# 3_BLE-T1-mcu.net
KiCad netlist of a schematic drawn in Altium Designer
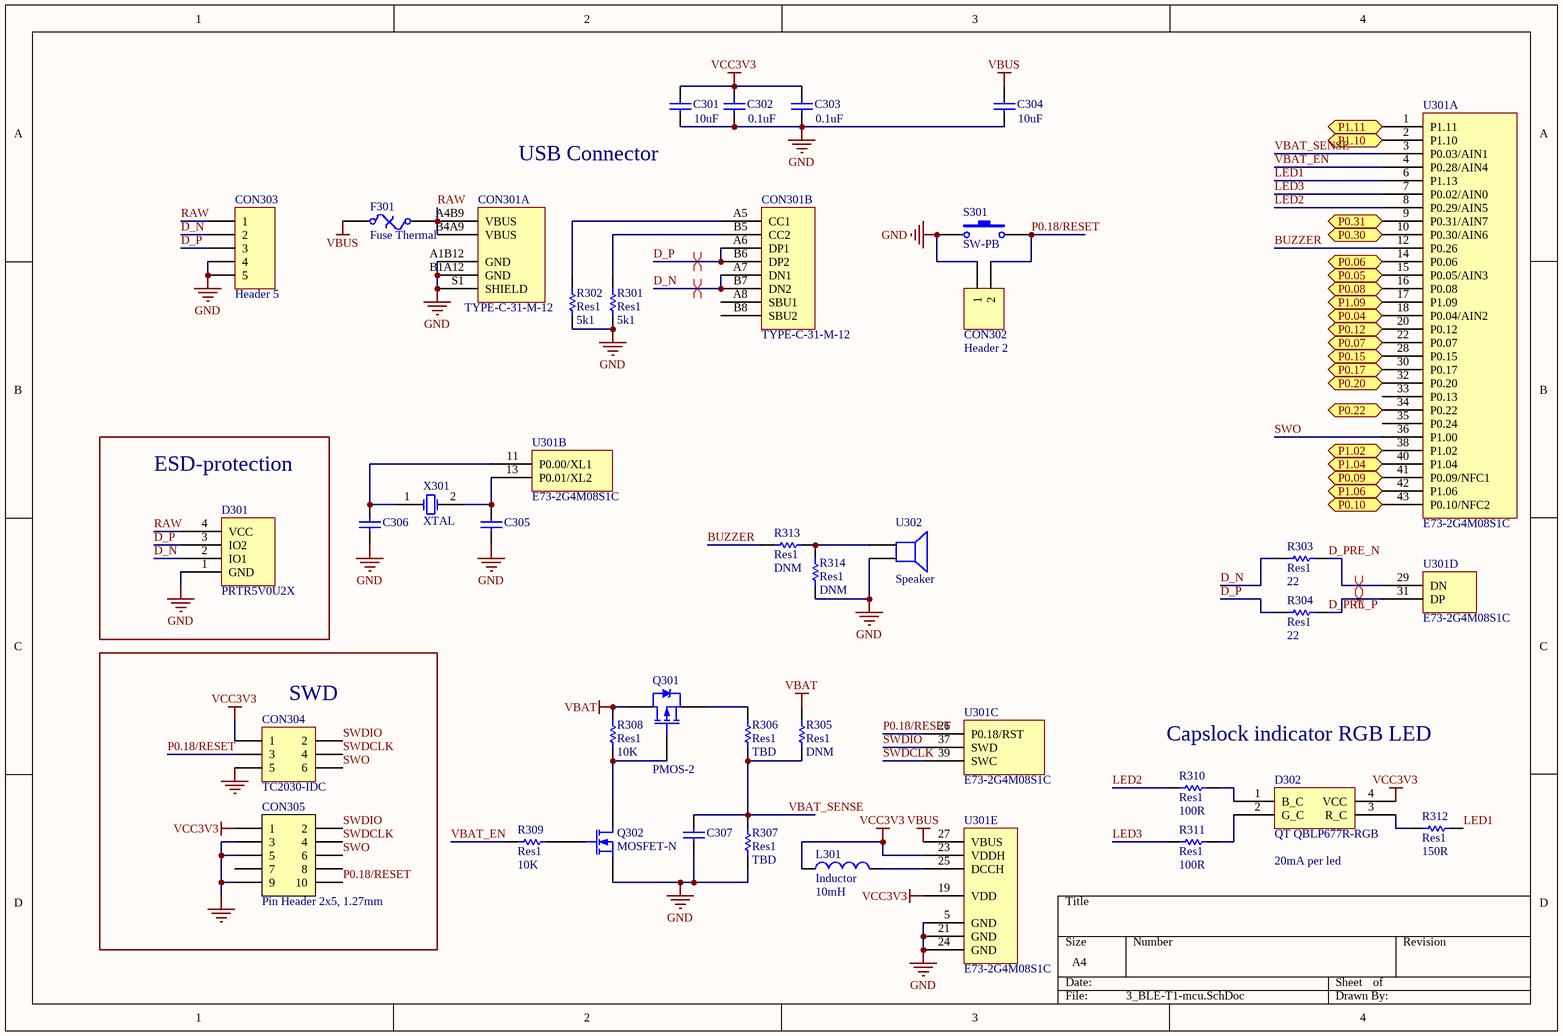
[diagram p0: 3_BLE-T1-mcu.SchDoc]

(export (version "E")
  (design (tool "Eeschema 10.0.6"))
  (components
    (comp (ref "C301")
      (value "10uF")
      (footprint "C1206[3216]")
      (description "Capacitor")
      (fields (field (name "MFG") "KEMET") (field (name "MRF.PART") "C3216X7R1C106KT000N"))
      (libsource (lib "Miscellaneous Devices") (part "Cap"))
    )
    (comp (ref "C302")
      (value "0.1uF")
      (footprint "C0603[1608]")
      (description "Capacitor")
      (fields (field (name "MFG") "KEMET") (field (name "MRF.PART") "CC0603KRX7R9BB104"))
      (libsource (lib "Miscellaneous Devices") (part "Cap"))
    )
    (comp (ref "C303")
      (value "0.1uF")
      (footprint "C0603[1608]")
      (description "Capacitor")
      (fields (field (name "MFG") "KEMET") (field (name "MRF.PART") "CC0603KRX7R9BB104"))
      (libsource (lib "Miscellaneous Devices") (part "Cap"))
    )
    (comp (ref "C304")
      (value "10uF")
      (footprint "C1206[3216]")
      (description "Capacitor")
      (fields (field (name "MFG") "KEMET") (field (name "MRF.PART") "C3216X7R1C106KT000N"))
      (libsource (lib "Miscellaneous Devices") (part "Cap"))
    )
    (comp (ref "C305")
      (value "~")
      (footprint "C0603[1608]")
      (description "Capacitor")
      (libsource (lib "Miscellaneous Devices") (part "Cap"))
    )
    (comp (ref "C306")
      (value "~")
      (footprint "C0603[1608]")
      (description "Capacitor")
      (libsource (lib "Miscellaneous Devices") (part "Cap"))
    )
    (comp (ref "C307")
      (value "~")
      (footprint "C0603[1608]")
      (description "Capacitor")
      (libsource (lib "Miscellaneous Devices") (part "Cap"))
    )
    (comp (ref "CON301")
      (value "TYPE-C-31-M-12")
      (footprint "TYPE-C-31-M-12")
      (fields (field (name "MFG") "Korean Hroparts Elec") (field (name "LCSC PART #") "C165948"))
      (libsource (lib "Schlib1") (part "TYPE-C-31-M-12"))
    )
    (comp (ref "CON302")
      (value "Header 2")
      (footprint "HDR1X2")
      (description "Header, 2-Pin")
      (fields (field (name "PUBLISHER") "Altium Limited"))
      (libsource (lib "Miscellaneous Connectors") (part "Header 2"))
    )
    (comp (ref "CON303")
      (value "Header 5")
      (footprint "JST SM04B-SRSS-TB")
      (description "JST for USB daughter board")
      (fields (field (name "MFG") "JST Sales America Inc.") (field (name "LCSC PART #") "C160404"))
      (libsource (lib "Miscellaneous Connectors") (part "Header 5"))
    )
    (comp (ref "CON304")
      (value "TC2030-IDC")
      (footprint "TC2030-IDC-NL")
      (description "Header, 3-Pin, Dual row")
      (libsource (lib "Miscellaneous Connectors") (part "Header 3X2"))
    )
    (comp (ref "CON305")
      (value "Pin Header 2x5, 1.27mm")
      (footprint "HDR_2x5-SMD-1.27mm-K")
      (description "Pin Header 2x5, 1.27mm (50mil), SMD, Keying Shroud")
      (fields (field (name "MFG") "Samtec Inc."))
      (libsource (lib "Nordic Passive DB") (part "CONN-2x5"))
    )
    (comp (ref "D301")
      (value "PRTR5V0U2X")
      (footprint "SOT190P237X120-4N")
      (fields
        (field (name "MFG") "Nexperia USA Inc.")
        (field (name "LCSC PART #") "C78442")
        (field (name "MRF.PART") "UET14A05L03")
      )
      (libsource (lib "Schlib1") (part "PRTR5V0U2X"))
    )
    (comp (ref "D302")
      (value "QT QBLP677R-RGB")
      (footprint "QT QBLP677R-RGB")
      (description "RGB LED")
      (fields (field (name "MFG") "QT Brightek (QTB)"))
      (libsource (lib "Keebs") (part "QT QBLP677R-RGB"))
    )
    (comp (ref "F301")
      (value "Fuse Thermal")
      (footprint "C1206[3216]")
      (description "Thermal Fuse")
      (fields (field (name "MFG") "Bel Fuse Inc.") (field (name "LCSC PART #") "C135338"))
      (libsource (lib "Miscellaneous Devices") (part "Fuse Thermal"))
    )
    (comp (ref "L301")
      (value "Inductor")
      (footprint "C0603[1608]")
      (fields (field (name "ALTIUM_VALUE") "10mH") (field (name "PUBLISHER") "Altium Limited"))
      (libsource (lib "Miscellaneous Devices") (part "Inductor"))
    )
    (comp (ref "Q301")
      (value "PMOS-2")
      (footprint "SOT-23-3")
      (description "P-Channel Power MOSFET")
      (fields (field (name "PUBLISHER") "Altium Limited"))
      (libsource (lib "Miscellaneous Devices") (part "PMOS-2"))
    )
    (comp (ref "Q302")
      (value "MOSFET-N")
      (footprint "SOT-23-3")
      (description "N-Channel MOSFET")
      (fields (field (name "PUBLISHER") "Altium Limited"))
      (libsource (lib "Miscellaneous Devices") (part "MOSFET-N"))
    )
    (comp (ref "R301")
      (value "Res1")
      (footprint "R0603[1608]")
      (description "Resistor")
      (fields
        (field (name "ALTIUM_VALUE") "5k1")
        (field (name "MFG") "Panasonic Electronic Components")
        (field (name "LCSC PART #") "C23186")
      )
      (libsource (lib "Miscellaneous Devices") (part "Res1"))
    )
    (comp (ref "R302")
      (value "Res1")
      (footprint "R0603[1608]")
      (description "Resistor")
      (fields
        (field (name "ALTIUM_VALUE") "5k1")
        (field (name "MFG") "Panasonic Electronic Components")
        (field (name "LCSC PART #") "C23186")
      )
      (libsource (lib "Miscellaneous Devices") (part "Res1"))
    )
    (comp (ref "R303")
      (value "Res1")
      (footprint "R0603[1608]")
      (description "Resistor")
      (fields
        (field (name "ALTIUM_VALUE") "22")
        (field (name "MFG") "Panasonic Electronic Components")
        (field (name "LCSC PART #") "C23345")
      )
      (libsource (lib "Miscellaneous Devices") (part "Res1"))
    )
    (comp (ref "R304")
      (value "Res1")
      (footprint "R0603[1608]")
      (description "Resistor")
      (fields
        (field (name "ALTIUM_VALUE") "22")
        (field (name "MFG") "Panasonic Electronic Components")
        (field (name "LCSC PART #") "C23345")
      )
      (libsource (lib "Miscellaneous Devices") (part "Res1"))
    )
    (comp (ref "R305")
      (value "Res1")
      (footprint "R0603[1608]")
      (description "Resistor")
      (fields (field (name "ALTIUM_VALUE") "DNM") (field (name "MFG") "TE Connectivity Passive Product"))
      (libsource (lib "Miscellaneous Devices") (part "Res1"))
    )
    (comp (ref "R306")
      (value "Res1")
      (footprint "R0603[1608]")
      (description "Resistor")
      (fields (field (name "ALTIUM_VALUE") "TBD") (field (name "MFG") "TE Connectivity Passive Product"))
      (libsource (lib "Miscellaneous Devices") (part "Res1"))
    )
    (comp (ref "R307")
      (value "Res1")
      (footprint "R0603[1608]")
      (description "Resistor")
      (fields (field (name "ALTIUM_VALUE") "TBD") (field (name "MFG") "TE Connectivity Passive Product"))
      (libsource (lib "Miscellaneous Devices") (part "Res1"))
    )
    (comp (ref "R308")
      (value "Res1")
      (footprint "R0603[1608]")
      (description "Resistor")
      (fields (field (name "ALTIUM_VALUE") "10K") (field (name "MFG") "TE Connectivity Passive Product"))
      (libsource (lib "Miscellaneous Devices") (part "Res1"))
    )
    (comp (ref "R309")
      (value "Res1")
      (footprint "R0603[1608]")
      (description "Resistor")
      (fields (field (name "ALTIUM_VALUE") "10K") (field (name "MFG") "TE Connectivity Passive Product"))
      (libsource (lib "Miscellaneous Devices") (part "Res1"))
    )
    (comp (ref "R310")
      (value "Res1")
      (footprint "R0603[1608]")
      (description "Resistor")
      (fields (field (name "ALTIUM_VALUE") "100R") (field (name "MFG") "TE Connectivity Passive Product"))
      (libsource (lib "Miscellaneous Devices") (part "Res1"))
    )
    (comp (ref "R311")
      (value "Res1")
      (footprint "R0603[1608]")
      (description "Resistor")
      (fields (field (name "ALTIUM_VALUE") "100R") (field (name "MFG") "TE Connectivity Passive Product"))
      (libsource (lib "Miscellaneous Devices") (part "Res1"))
    )
    (comp (ref "R312")
      (value "Res1")
      (footprint "R0603[1608]")
      (description "Resistor")
      (fields (field (name "ALTIUM_VALUE") "150R") (field (name "MFG") "TE Connectivity Passive Product"))
      (libsource (lib "Miscellaneous Devices") (part "Res1"))
    )
    (comp (ref "R313")
      (value "Res1")
      (footprint "R0603[1608]")
      (description "Resistor")
      (fields
        (field (name "ALTIUM_VALUE") "DNM")
        (field (name "MFG") "Panasonic Electronic Components")
        (field (name "LCSC PART #") "C23345")
      )
      (libsource (lib "Miscellaneous Devices") (part "Res1"))
    )
    (comp (ref "R314")
      (value "Res1")
      (footprint "R0603[1608]")
      (description "Resistor")
      (fields
        (field (name "ALTIUM_VALUE") "DNM")
        (field (name "MFG") "Panasonic Electronic Components")
        (field (name "LCSC PART #") "C23345")
      )
      (libsource (lib "Miscellaneous Devices") (part "Res1"))
    )
    (comp (ref "S301")
      (value "SW-PB")
      (footprint "Combo switch")
      (description "Switch")
      (fields (field (name "MFG") "C&K") (field (name "MRF.PART") "TS-1187A-C-D-B"))
      (libsource (lib "Miscellaneous Devices") (part "SW-PB"))
    )
    (comp (ref "U301")
      (value "E73-2G4M08S1C")
      (footprint "E73-2G4M08S1C BLE-T1")
      (libsource (lib "Keebs") (part "E73-2G4M08S1C"))
    )
    (comp (ref "U302")
      (value "Speaker")
      (footprint "buzzer 12x12")
      (description "Loudspeaker")
      (fields (field (name "PUBLISHER") "Altium Limited"))
      (libsource (lib "Miscellaneous Devices") (part "Speaker"))
    )
    (comp (ref "X301")
      (value "XTAL")
      (footprint "Seiko Epson Q13FC1350000400")
      (description "Crystal Oscillator")
      (fields (field (name "LCSC PART #") "C32346") (field (name "MRF.PART") "Q13FC1350000400"))
      (libsource (lib "Miscellaneous Devices") (part "XTAL"))
    )
  )
  (nets
    (net (code "1") (name "/BUZZER") (class "Default")
      (node (ref "R313") (pin "1") (pinfunction "1_1") (pintype "passive"))
      (node (ref "U301") (pin "12") (pinfunction "P0.26_12") (pintype "passive"))
    )
    (net (code "2") (name "/D_N") (class "Default")
      (node (ref "CON301") (pin "A7") (pinfunction "DN1_A7") (pintype "passive"))
      (node (ref "CON301") (pin "B7") (pinfunction "DN2_B7") (pintype "passive"))
      (node (ref "CON303") (pin "2") (pinfunction "2_2") (pintype "passive"))
      (node (ref "D301") (pin "2") (pinfunction "IO1_2") (pintype "passive"))
      (node (ref "R303") (pin "2") (pinfunction "2_2") (pintype "passive"))
    )
    (net (code "3") (name "/D_P") (class "Default")
      (node (ref "CON301") (pin "A6") (pinfunction "DP1_A6") (pintype "passive"))
      (node (ref "CON301") (pin "B6") (pinfunction "DP2_B6") (pintype "passive"))
      (node (ref "CON303") (pin "3") (pinfunction "3_3") (pintype "passive"))
      (node (ref "D301") (pin "3") (pinfunction "IO2_3") (pintype "passive"))
      (node (ref "R304") (pin "2") (pinfunction "2_2") (pintype "passive"))
    )
    (net (code "4") (name "/D_PRE_N") (class "Default")
      (node (ref "R303") (pin "1") (pinfunction "1_1") (pintype "passive"))
      (node (ref "U301") (pin "29") (pinfunction "DN_29") (pintype "passive"))
    )
    (net (code "5") (name "/D_PRE_P") (class "Default")
      (node (ref "R304") (pin "1") (pinfunction "1_1") (pintype "passive"))
      (node (ref "U301") (pin "31") (pinfunction "DP_31") (pintype "passive"))
    )
    (net (code "6") (name "/LED1") (class "Default")
      (node (ref "R312") (pin "1") (pinfunction "1_1") (pintype "passive"))
      (node (ref "U301") (pin "6") (pinfunction "P1.13_6") (pintype "passive"))
    )
    (net (code "7") (name "/LED2") (class "Default")
      (node (ref "R310") (pin "2") (pinfunction "2_2") (pintype "passive"))
      (node (ref "U301") (pin "8") (pinfunction "P0.29/AIN5_8") (pintype "passive"))
    )
    (net (code "8") (name "/LED3") (class "Default")
      (node (ref "R311") (pin "2") (pinfunction "2_2") (pintype "passive"))
      (node (ref "U301") (pin "7") (pinfunction "P0.02/AIN0_7") (pintype "passive"))
    )
    (net (code "9") (name "/P0.04") (class "Default")
      (node (ref "U301") (pin "18") (pinfunction "P0.04/AIN2_18") (pintype "passive"))
    )
    (net (code "10") (name "/P0.05") (class "Default")
      (node (ref "U301") (pin "15") (pinfunction "P0.05/AIN3_15") (pintype "passive"))
    )
    (net (code "11") (name "/P0.06") (class "Default")
      (node (ref "U301") (pin "14") (pinfunction "P0.06_14") (pintype "passive"))
    )
    (net (code "12") (name "/P0.07") (class "Default")
      (node (ref "U301") (pin "22") (pinfunction "P0.07_22") (pintype "passive"))
    )
    (net (code "13") (name "/P0.08") (class "Default")
      (node (ref "U301") (pin "16") (pinfunction "P0.08_16") (pintype "passive"))
    )
    (net (code "14") (name "/P0.09") (class "Default")
      (node (ref "U301") (pin "41") (pinfunction "P0.09/NFC1_41") (pintype "passive"))
    )
    (net (code "15") (name "/P0.10") (class "Default")
      (node (ref "U301") (pin "43") (pinfunction "P0.10/NFC2_43") (pintype "passive"))
    )
    (net (code "16") (name "/P0.12") (class "Default")
      (node (ref "U301") (pin "20") (pinfunction "P0.12_20") (pintype "passive"))
    )
    (net (code "17") (name "/P0.15") (class "Default")
      (node (ref "U301") (pin "28") (pinfunction "P0.15_28") (pintype "passive"))
    )
    (net (code "18") (name "/P0.17") (class "Default")
      (node (ref "U301") (pin "30") (pinfunction "P0.17_30") (pintype "passive"))
    )
    (net (code "19") (name "/P0.18{slash}RESET") (class "Default")
      (node (ref "CON302") (pin "2") (pinfunction "2_2") (pintype "passive"))
      (node (ref "CON304") (pin "3") (pinfunction "3_3") (pintype "passive"))
      (node (ref "CON305") (pin "10") (pinfunction "10_10") (pintype "passive"))
      (node (ref "S301") (pin "2") (pinfunction "2_2") (pintype "passive"))
      (node (ref "U301") (pin "26") (pinfunction "P0.18/RST_26") (pintype "passive"))
    )
    (net (code "20") (name "/P0.20") (class "Default")
      (node (ref "U301") (pin "32") (pinfunction "P0.20_32") (pintype "passive"))
    )
    (net (code "21") (name "/P0.22") (class "Default")
      (node (ref "U301") (pin "34") (pinfunction "P0.22_34") (pintype "passive"))
    )
    (net (code "22") (name "/P0.30") (class "Default")
      (node (ref "U301") (pin "10") (pinfunction "P0.30/AIN6_10") (pintype "passive"))
    )
    (net (code "23") (name "/P0.31") (class "Default")
      (node (ref "U301") (pin "9") (pinfunction "P0.31/AIN7_9") (pintype "passive"))
    )
    (net (code "24") (name "/P1.02") (class "Default")
      (node (ref "U301") (pin "38") (pinfunction "P1.02_38") (pintype "passive"))
    )
    (net (code "25") (name "/P1.04") (class "Default")
      (node (ref "U301") (pin "40") (pinfunction "P1.04_40") (pintype "passive"))
    )
    (net (code "26") (name "/P1.06") (class "Default")
      (node (ref "U301") (pin "42") (pinfunction "P1.06_42") (pintype "passive"))
    )
    (net (code "27") (name "/P1.09") (class "Default")
      (node (ref "U301") (pin "17") (pinfunction "P1.09_17") (pintype "passive"))
    )
    (net (code "28") (name "/P1.10") (class "Default")
      (node (ref "U301") (pin "2") (pinfunction "P1.10_2") (pintype "passive"))
    )
    (net (code "29") (name "/P1.11") (class "Default")
      (node (ref "U301") (pin "1") (pinfunction "P1.11_1") (pintype "passive"))
    )
    (net (code "30") (name "/RAW") (class "Default")
      (node (ref "CON301") (pin "A4B9") (pinfunction "VBUS_A4B9") (pintype "passive"))
      (node (ref "CON301") (pin "B4A9") (pinfunction "VBUS_B4A9") (pintype "passive"))
      (node (ref "CON303") (pin "1") (pinfunction "1_1") (pintype "passive"))
      (node (ref "D301") (pin "4") (pinfunction "VCC_4") (pintype "passive"))
      (node (ref "F301") (pin "2") (pinfunction "2_2") (pintype "passive"))
    )
    (net (code "31") (name "/SWDCLK") (class "Default")
      (node (ref "CON304") (pin "4") (pinfunction "4_4") (pintype "passive"))
      (node (ref "CON305") (pin "4") (pinfunction "4_4") (pintype "passive"))
      (node (ref "U301") (pin "39") (pinfunction "SWC_39") (pintype "passive"))
    )
    (net (code "32") (name "/SWDIO") (class "Default")
      (node (ref "CON304") (pin "2") (pinfunction "2_2") (pintype "passive"))
      (node (ref "CON305") (pin "2") (pinfunction "2_2") (pintype "passive"))
      (node (ref "U301") (pin "37") (pinfunction "SWD_37") (pintype "passive"))
    )
    (net (code "33") (name "/SWO") (class "Default")
      (node (ref "CON304") (pin "6") (pinfunction "6_6") (pintype "passive"))
      (node (ref "CON305") (pin "6") (pinfunction "6_6") (pintype "passive"))
      (node (ref "U301") (pin "36") (pinfunction "P1.00_36") (pintype "passive"))
    )
    (net (code "34") (name "/VBAT_EN") (class "Default")
      (node (ref "R309") (pin "2") (pinfunction "2_2") (pintype "passive"))
      (node (ref "U301") (pin "4") (pinfunction "P0.28/AIN4_4") (pintype "passive"))
    )
    (net (code "35") (name "/VBAT_SENSE") (class "Default")
      (node (ref "C307") (pin "2") (pinfunction "2_2") (pintype "passive"))
      (node (ref "R305") (pin "1") (pinfunction "1_1") (pintype "passive"))
      (node (ref "R306") (pin "1") (pinfunction "1_1") (pintype "passive"))
      (node (ref "R307") (pin "2") (pinfunction "2_2") (pintype "passive"))
      (node (ref "U301") (pin "3") (pinfunction "P0.03/AIN1_3") (pintype "passive"))
    )
    (net (code "36") (name "GND") (class "Default")
      (node (ref "C301") (pin "1") (pinfunction "1_1") (pintype "passive"))
      (node (ref "C302") (pin "1") (pinfunction "1_1") (pintype "passive"))
      (node (ref "C303") (pin "1") (pinfunction "1_1") (pintype "passive"))
      (node (ref "C304") (pin "1") (pinfunction "1_1") (pintype "passive"))
      (node (ref "C305") (pin "1") (pinfunction "1_1") (pintype "passive"))
      (node (ref "C306") (pin "1") (pinfunction "1_1") (pintype "passive"))
      (node (ref "C307") (pin "1") (pinfunction "1_1") (pintype "passive"))
      (node (ref "CON301") (pin "A1B12") (pinfunction "GND_A1B12") (pintype "passive"))
      (node (ref "CON301") (pin "B1A12") (pinfunction "GND_B1A12") (pintype "passive"))
      (node (ref "CON301") (pin "S1") (pinfunction "SHIELD_S1") (pintype "passive"))
      (node (ref "CON302") (pin "1") (pinfunction "1_1") (pintype "passive"))
      (node (ref "CON303") (pin "4") (pinfunction "4_4") (pintype "passive"))
      (node (ref "CON303") (pin "5") (pinfunction "5_5") (pintype "passive"))
      (node (ref "CON304") (pin "5") (pinfunction "5_5") (pintype "passive"))
      (node (ref "CON305") (pin "3") (pinfunction "3_3") (pintype "passive"))
      (node (ref "CON305") (pin "5") (pinfunction "5_5") (pintype "passive"))
      (node (ref "CON305") (pin "9") (pinfunction "9_9") (pintype "passive"))
      (node (ref "D301") (pin "1") (pinfunction "GND_1") (pintype "passive"))
      (node (ref "Q302") (pin "2") (pinfunction "S_2") (pintype "passive"))
      (node (ref "R301") (pin "2") (pinfunction "2_2") (pintype "passive"))
      (node (ref "R302") (pin "2") (pinfunction "2_2") (pintype "passive"))
      (node (ref "R307") (pin "1") (pinfunction "1_1") (pintype "passive"))
      (node (ref "R314") (pin "1") (pinfunction "1_1") (pintype "passive"))
      (node (ref "S301") (pin "1") (pinfunction "1_1") (pintype "passive"))
      (node (ref "U301") (pin "21") (pinfunction "GND_21") (pintype "passive"))
      (node (ref "U301") (pin "24") (pinfunction "GND_24") (pintype "passive"))
      (node (ref "U301") (pin "5") (pinfunction "GND_5") (pintype "passive"))
      (node (ref "U302") (pin "2") (pinfunction "2_2") (pintype "passive"))
    )
    (net (code "37") (name "Net-(CON301B-CC1)") (class "Default")
      (node (ref "CON301") (pin "A5") (pinfunction "CC1_A5") (pintype "passive"))
      (node (ref "R302") (pin "1") (pinfunction "1_1") (pintype "passive"))
    )
    (net (code "38") (name "Net-(CON301B-CC2)") (class "Default")
      (node (ref "CON301") (pin "B5") (pinfunction "CC2_B5") (pintype "passive"))
      (node (ref "R301") (pin "1") (pinfunction "1_1") (pintype "passive"))
    )
    (net (code "39") (name "Net-(D302-B_C)") (class "Default")
      (node (ref "D302") (pin "1") (pinfunction "B_C_1") (pintype "passive"))
      (node (ref "R310") (pin "1") (pinfunction "1_1") (pintype "passive"))
    )
    (net (code "40") (name "Net-(D302-G_C)") (class "Default")
      (node (ref "D302") (pin "2") (pinfunction "G_C_2") (pintype "passive"))
      (node (ref "R311") (pin "1") (pinfunction "1_1") (pintype "passive"))
    )
    (net (code "41") (name "Net-(D302-R_C)") (class "Default")
      (node (ref "D302") (pin "3") (pinfunction "R_C_3") (pintype "passive"))
      (node (ref "R312") (pin "2") (pinfunction "2_2") (pintype "passive"))
    )
    (net (code "42") (name "Net-(Q301-G)") (class "Default")
      (node (ref "Q301") (pin "1") (pinfunction "G_1") (pintype "passive"))
      (node (ref "Q302") (pin "3") (pinfunction "D_3") (pintype "passive"))
      (node (ref "R308") (pin "1") (pinfunction "1_1") (pintype "passive"))
    )
    (net (code "43") (name "Net-(Q301-S)") (class "Default")
      (node (ref "Q301") (pin "2") (pinfunction "S_2") (pintype "passive"))
      (node (ref "R306") (pin "2") (pinfunction "2_2") (pintype "passive"))
    )
    (net (code "44") (name "Net-(Q302-G)") (class "Default")
      (node (ref "Q302") (pin "1") (pinfunction "G_1") (pintype "passive"))
      (node (ref "R309") (pin "1") (pinfunction "1_1") (pintype "passive"))
    )
    (net (code "45") (name "Net-(R313-Pad2)") (class "Default")
      (node (ref "R313") (pin "2") (pinfunction "2_2") (pintype "passive"))
      (node (ref "R314") (pin "2") (pinfunction "2_2") (pintype "passive"))
      (node (ref "U302") (pin "1") (pinfunction "1_1") (pintype "passive"))
    )
    (net (code "46") (name "Net-(U301B-P0.00{slash}XL1)") (class "Default")
      (node (ref "C306") (pin "2") (pinfunction "2_2") (pintype "passive"))
      (node (ref "U301") (pin "11") (pinfunction "P0.00/XL1_11") (pintype "passive"))
      (node (ref "X301") (pin "1") (pinfunction "OSC1_1") (pintype "passive"))
    )
    (net (code "47") (name "Net-(U301B-P0.01{slash}XL2)") (class "Default")
      (node (ref "C305") (pin "2") (pinfunction "2_2") (pintype "passive"))
      (node (ref "U301") (pin "13") (pinfunction "P0.01/XL2_13") (pintype "passive"))
      (node (ref "X301") (pin "2") (pinfunction "OSC2_2") (pintype "passive"))
    )
    (net (code "48") (name "Net-(U301E-DCCH)") (class "Default")
      (node (ref "L301") (pin "2") (pinfunction "2_2") (pintype "passive"))
      (node (ref "U301") (pin "25") (pinfunction "DCCH_25") (pintype "passive"))
    )
    (net (code "49") (name "VBAT") (class "Default")
      (node (ref "Q301") (pin "3") (pinfunction "D_3") (pintype "passive"))
      (node (ref "R305") (pin "2") (pinfunction "2_2") (pintype "passive"))
      (node (ref "R308") (pin "2") (pinfunction "2_2") (pintype "passive"))
    )
    (net (code "50") (name "VBUS") (class "Default")
      (node (ref "C304") (pin "2") (pinfunction "2_2") (pintype "passive"))
      (node (ref "F301") (pin "1") (pinfunction "1_1") (pintype "passive"))
      (node (ref "U301") (pin "27") (pinfunction "VBUS_27") (pintype "passive"))
    )
    (net (code "51") (name "VCC3V3") (class "Default")
      (node (ref "C301") (pin "2") (pinfunction "2_2") (pintype "passive"))
      (node (ref "C302") (pin "2") (pinfunction "2_2") (pintype "passive"))
      (node (ref "C303") (pin "2") (pinfunction "2_2") (pintype "passive"))
      (node (ref "CON304") (pin "1") (pinfunction "1_1") (pintype "passive"))
      (node (ref "CON305") (pin "1") (pinfunction "1_1") (pintype "passive"))
      (node (ref "D302") (pin "4") (pinfunction "VCC_4") (pintype "passive"))
      (node (ref "L301") (pin "1") (pinfunction "1_1") (pintype "passive"))
      (node (ref "U301") (pin "19") (pinfunction "VDD_19") (pintype "passive"))
      (node (ref "U301") (pin "23") (pinfunction "VDDH_23") (pintype "passive"))
    )
    (net (code "52") (name "unconnected-(CON301B-SBU1-PadA8)") (class "Default")
      (node (ref "CON301") (pin "A8") (pinfunction "SBU1_A8") (pintype "passive"))
    )
    (net (code "53") (name "unconnected-(CON301B-SBU2-PadB8)") (class "Default")
      (node (ref "CON301") (pin "B8") (pinfunction "SBU2_B8") (pintype "passive"))
    )
    (net (code "54") (name "unconnected-(CON305-Pad7)") (class "Default")
      (node (ref "CON305") (pin "7") (pinfunction "7_7") (pintype "passive"))
    )
    (net (code "55") (name "unconnected-(CON305-Pad8)") (class "Default")
      (node (ref "CON305") (pin "8") (pinfunction "8_8") (pintype "passive"))
    )
    (net (code "56") (name "unconnected-(U301A-P0.13-Pad33)") (class "Default")
      (node (ref "U301") (pin "33") (pinfunction "P0.13_33") (pintype "passive"))
    )
    (net (code "57") (name "unconnected-(U301A-P0.24-Pad35)") (class "Default")
      (node (ref "U301") (pin "35") (pinfunction "P0.24_35") (pintype "passive"))
    )
  )
)
